# moduloComunicacao3.net
KiCad netlist of a schematic drawn in EAGLE
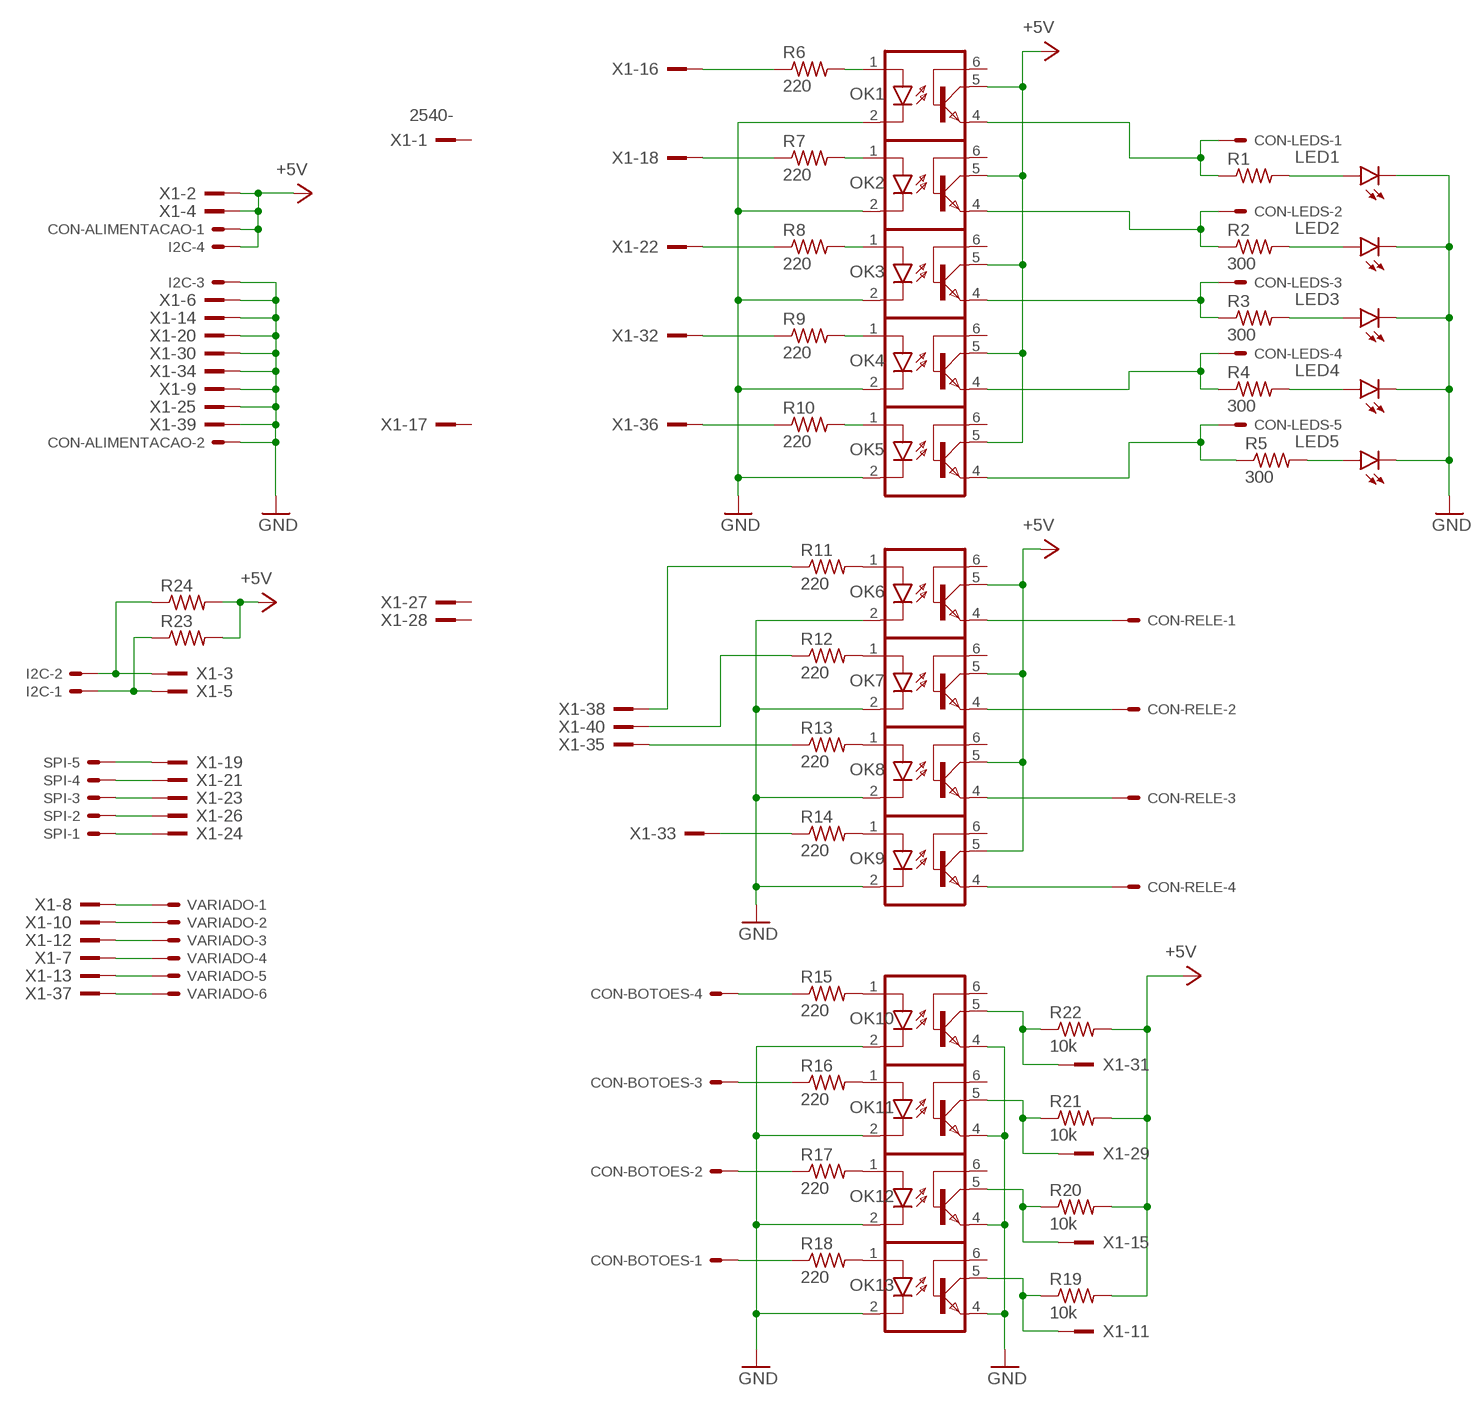
[diagram p0: schematic, sheet 1]

(export (version "E")
  (design (tool "Eeschema 10.0.6"))
  (components
    (comp (ref "CON-ALIMENTACAO")
      (value "22-23-2021")
      (footprint "eagle-import:22-23-2021")
      (fields (field (name "MF") "MOLEX"))
      (libsource (lib "eagle-import") (part "22-23-2021"))
    )
    (comp (ref "CON-BOTOES")
      (value "22-23-2041")
      (footprint "eagle-import:22-23-2041")
      (fields (field (name "MF") "MOLEX"))
      (libsource (lib "eagle-import") (part "22-23-2041"))
    )
    (comp (ref "CON-LEDS")
      (value "22-23-2051")
      (footprint "eagle-import:22-23-2051")
      (fields (field (name "MF") "MOLEX"))
      (libsource (lib "eagle-import") (part "22-23-2051"))
    )
    (comp (ref "CON-RELE")
      (value "22-23-2041")
      (footprint "eagle-import:22-23-2041")
      (fields (field (name "MF") "MOLEX"))
      (libsource (lib "eagle-import") (part "22-23-2041"))
    )
    (comp (ref "I2C")
      (value "22-23-2041")
      (footprint "eagle-import:22-23-2041")
      (fields (field (name "MF") "MOLEX"))
      (libsource (lib "eagle-import") (part "22-23-2041"))
    )
    (comp (ref "LED1")
      (value "LED5MM")
      (footprint "eagle-import:LED5MM")
      (libsource (lib "eagle-import") (part "LED5MM"))
    )
    (comp (ref "LED2")
      (value "LED5MM")
      (footprint "eagle-import:LED5MM")
      (libsource (lib "eagle-import") (part "LED5MM"))
    )
    (comp (ref "LED3")
      (value "LED5MM")
      (footprint "eagle-import:LED5MM")
      (libsource (lib "eagle-import") (part "LED5MM"))
    )
    (comp (ref "LED4")
      (value "LED5MM")
      (footprint "eagle-import:LED5MM")
      (libsource (lib "eagle-import") (part "LED5MM"))
    )
    (comp (ref "LED5")
      (value "LED5MM")
      (footprint "eagle-import:LED5MM")
      (libsource (lib "eagle-import") (part "LED5MM"))
    )
    (comp (ref "OK1")
      (value "4N25M")
      (footprint "eagle-import:DIL06")
      (fields (field (name "MPN") "4N25-M"))
      (libsource (lib "eagle-import") (part "4N?M25"))
    )
    (comp (ref "OK2")
      (value "4N25M")
      (footprint "eagle-import:DIL06")
      (fields (field (name "MPN") "4N25-M"))
      (libsource (lib "eagle-import") (part "4N?M25"))
    )
    (comp (ref "OK3")
      (value "4N25M")
      (footprint "eagle-import:DIL06")
      (fields (field (name "MPN") "4N25-M"))
      (libsource (lib "eagle-import") (part "4N?M25"))
    )
    (comp (ref "OK4")
      (value "4N25M")
      (footprint "eagle-import:DIL06")
      (fields (field (name "MPN") "4N25-M"))
      (libsource (lib "eagle-import") (part "4N?M25"))
    )
    (comp (ref "OK5")
      (value "4N25M")
      (footprint "eagle-import:DIL06")
      (fields (field (name "MPN") "4N25-M"))
      (libsource (lib "eagle-import") (part "4N?M25"))
    )
    (comp (ref "OK6")
      (value "4N25M")
      (footprint "eagle-import:DIL06")
      (fields (field (name "MPN") "4N25-M"))
      (libsource (lib "eagle-import") (part "4N?M25"))
    )
    (comp (ref "OK7")
      (value "4N25M")
      (footprint "eagle-import:DIL06")
      (fields (field (name "MPN") "4N25-M"))
      (libsource (lib "eagle-import") (part "4N?M25"))
    )
    (comp (ref "OK8")
      (value "4N25M")
      (footprint "eagle-import:DIL06")
      (fields (field (name "MPN") "4N25-M"))
      (libsource (lib "eagle-import") (part "4N?M25"))
    )
    (comp (ref "OK9")
      (value "4N25M")
      (footprint "eagle-import:DIL06")
      (fields (field (name "MPN") "4N25-M"))
      (libsource (lib "eagle-import") (part "4N?M25"))
    )
    (comp (ref "OK10")
      (value "4N25M")
      (footprint "eagle-import:DIL06")
      (fields (field (name "MPN") "4N25-M"))
      (libsource (lib "eagle-import") (part "4N?M25"))
    )
    (comp (ref "OK11")
      (value "4N25M")
      (footprint "eagle-import:DIL06")
      (fields (field (name "MPN") "4N25-M"))
      (libsource (lib "eagle-import") (part "4N?M25"))
    )
    (comp (ref "OK12")
      (value "4N25M")
      (footprint "eagle-import:DIL06")
      (fields (field (name "MPN") "4N25-M"))
      (libsource (lib "eagle-import") (part "4N?M25"))
    )
    (comp (ref "OK13")
      (value "4N25M")
      (footprint "eagle-import:DIL06")
      (fields (field (name "MPN") "4N25-M"))
      (libsource (lib "eagle-import") (part "4N?M25"))
    )
    (comp (ref "R1")
      (value "R-US_0207/12")
      (footprint "eagle-import:0207_12")
      (libsource (lib "eagle-import") (part "R-US_0207/12"))
    )
    (comp (ref "R2")
      (value "300")
      (footprint "eagle-import:0207_12")
      (libsource (lib "eagle-import") (part "R-US_0207/12"))
    )
    (comp (ref "R3")
      (value "300")
      (footprint "eagle-import:0207_12")
      (libsource (lib "eagle-import") (part "R-US_0207/12"))
    )
    (comp (ref "R4")
      (value "300")
      (footprint "eagle-import:0207_12")
      (libsource (lib "eagle-import") (part "R-US_0207/12"))
    )
    (comp (ref "R5")
      (value "300")
      (footprint "eagle-import:0207_12")
      (libsource (lib "eagle-import") (part "R-US_0207/12"))
    )
    (comp (ref "R6")
      (value "220")
      (footprint "eagle-import:0204_7")
      (libsource (lib "eagle-import") (part "R-US_0204/7"))
    )
    (comp (ref "R7")
      (value "220")
      (footprint "eagle-import:0204_7")
      (libsource (lib "eagle-import") (part "R-US_0204/7"))
    )
    (comp (ref "R8")
      (value "220")
      (footprint "eagle-import:0204_7")
      (libsource (lib "eagle-import") (part "R-US_0204/7"))
    )
    (comp (ref "R9")
      (value "220")
      (footprint "eagle-import:0204_7")
      (libsource (lib "eagle-import") (part "R-US_0204/7"))
    )
    (comp (ref "R10")
      (value "220")
      (footprint "eagle-import:0204_7")
      (libsource (lib "eagle-import") (part "R-US_0204/7"))
    )
    (comp (ref "R11")
      (value "220")
      (footprint "eagle-import:0204_7")
      (libsource (lib "eagle-import") (part "R-US_0204/7"))
    )
    (comp (ref "R12")
      (value "220")
      (footprint "eagle-import:0204_7")
      (libsource (lib "eagle-import") (part "R-US_0204/7"))
    )
    (comp (ref "R13")
      (value "220")
      (footprint "eagle-import:0204_7")
      (libsource (lib "eagle-import") (part "R-US_0204/7"))
    )
    (comp (ref "R14")
      (value "220")
      (footprint "eagle-import:0204_7")
      (libsource (lib "eagle-import") (part "R-US_0204/7"))
    )
    (comp (ref "R15")
      (value "220")
      (footprint "eagle-import:0207_10")
      (libsource (lib "eagle-import") (part "R-US_0207/10"))
    )
    (comp (ref "R16")
      (value "220")
      (footprint "eagle-import:0207_10")
      (libsource (lib "eagle-import") (part "R-US_0207/10"))
    )
    (comp (ref "R17")
      (value "220")
      (footprint "eagle-import:0207_10")
      (libsource (lib "eagle-import") (part "R-US_0207/10"))
    )
    (comp (ref "R18")
      (value "220")
      (footprint "eagle-import:0207_10")
      (libsource (lib "eagle-import") (part "R-US_0207/10"))
    )
    (comp (ref "R19")
      (value "10k")
      (footprint "eagle-import:0204_7")
      (libsource (lib "eagle-import") (part "R-US_0204/7"))
    )
    (comp (ref "R20")
      (value "10k")
      (footprint "eagle-import:0204_7")
      (libsource (lib "eagle-import") (part "R-US_0204/7"))
    )
    (comp (ref "R21")
      (value "10k")
      (footprint "eagle-import:0204_7")
      (libsource (lib "eagle-import") (part "R-US_0204/7"))
    )
    (comp (ref "R22")
      (value "10k")
      (footprint "eagle-import:0204_7")
      (libsource (lib "eagle-import") (part "R-US_0204/7"))
    )
    (comp (ref "R23")
      (value "R-US_0204/5")
      (footprint "eagle-import:0204_5")
      (libsource (lib "eagle-import") (part "R-US_0204/5"))
    )
    (comp (ref "R24")
      (value "R-US_0204/5")
      (footprint "eagle-import:0204_5")
      (libsource (lib "eagle-import") (part "R-US_0204/5"))
    )
    (comp (ref "SPI")
      (value "22-23-2051")
      (footprint "eagle-import:22-23-2051")
      (fields (field (name "MF") "MOLEX"))
      (libsource (lib "eagle-import") (part "22-23-2051"))
    )
    (comp (ref "VARIADO")
      (value "22-23-2061")
      (footprint "eagle-import:22-23-2061")
      (fields (field (name "MF") "MOLEX"))
      (libsource (lib "eagle-import") (part "22-23-2061"))
    )
    (comp (ref "X1")
      (value "2540-")
      (footprint "eagle-import:PAK100_2500-40")
      (libsource (lib "eagle-import") (part "2540-"))
    )
  )
  (nets
    (net (code "1") (name "+5V") (class "Default")
      (node (ref "CON-ALIMENTACAO") (pin "1") (pinfunction "S_1") (pintype "passive"))
      (node (ref "I2C") (pin "4") (pinfunction "S_4") (pintype "passive"))
      (node (ref "OK1") (pin "5") (pinfunction "COL_5") (pintype "passive"))
      (node (ref "OK2") (pin "5") (pinfunction "COL_5") (pintype "passive"))
      (node (ref "OK3") (pin "5") (pinfunction "COL_5") (pintype "passive"))
      (node (ref "OK4") (pin "5") (pinfunction "COL_5") (pintype "passive"))
      (node (ref "OK5") (pin "5") (pinfunction "COL_5") (pintype "passive"))
      (node (ref "OK6") (pin "5") (pinfunction "COL_5") (pintype "passive"))
      (node (ref "OK7") (pin "5") (pinfunction "COL_5") (pintype "passive"))
      (node (ref "OK8") (pin "5") (pinfunction "COL_5") (pintype "passive"))
      (node (ref "OK9") (pin "5") (pinfunction "COL_5") (pintype "passive"))
      (node (ref "R19") (pin "2") (pinfunction "2_2") (pintype "passive"))
      (node (ref "R20") (pin "2") (pinfunction "2_2") (pintype "passive"))
      (node (ref "R21") (pin "2") (pinfunction "2_2") (pintype "passive"))
      (node (ref "R22") (pin "2") (pinfunction "2_2") (pintype "passive"))
      (node (ref "R23") (pin "2") (pinfunction "2_2") (pintype "passive"))
      (node (ref "R24") (pin "2") (pinfunction "2_2") (pintype "passive"))
      (node (ref "X1") (pin "2") (pinfunction "KL_2") (pintype "passive"))
      (node (ref "X1") (pin "4") (pinfunction "KL_4") (pintype "passive"))
    )
    (net (code "2") (name "GND") (class "Default")
      (node (ref "CON-ALIMENTACAO") (pin "2") (pinfunction "S_2") (pintype "passive"))
      (node (ref "I2C") (pin "3") (pinfunction "S_3") (pintype "passive"))
      (node (ref "LED1") (pin "K") (pinfunction "C_K") (pintype "passive"))
      (node (ref "LED2") (pin "K") (pinfunction "C_K") (pintype "passive"))
      (node (ref "LED3") (pin "K") (pinfunction "C_K") (pintype "passive"))
      (node (ref "LED4") (pin "K") (pinfunction "C_K") (pintype "passive"))
      (node (ref "LED5") (pin "K") (pinfunction "C_K") (pintype "passive"))
      (node (ref "OK1") (pin "2") (pinfunction "C_2") (pintype "passive"))
      (node (ref "OK10") (pin "2") (pinfunction "C_2") (pintype "passive"))
      (node (ref "OK10") (pin "4") (pinfunction "EMI_4") (pintype "passive"))
      (node (ref "OK11") (pin "2") (pinfunction "C_2") (pintype "passive"))
      (node (ref "OK11") (pin "4") (pinfunction "EMI_4") (pintype "passive"))
      (node (ref "OK12") (pin "2") (pinfunction "C_2") (pintype "passive"))
      (node (ref "OK12") (pin "4") (pinfunction "EMI_4") (pintype "passive"))
      (node (ref "OK13") (pin "2") (pinfunction "C_2") (pintype "passive"))
      (node (ref "OK13") (pin "4") (pinfunction "EMI_4") (pintype "passive"))
      (node (ref "OK2") (pin "2") (pinfunction "C_2") (pintype "passive"))
      (node (ref "OK3") (pin "2") (pinfunction "C_2") (pintype "passive"))
      (node (ref "OK4") (pin "2") (pinfunction "C_2") (pintype "passive"))
      (node (ref "OK5") (pin "2") (pinfunction "C_2") (pintype "passive"))
      (node (ref "OK6") (pin "2") (pinfunction "C_2") (pintype "passive"))
      (node (ref "OK7") (pin "2") (pinfunction "C_2") (pintype "passive"))
      (node (ref "OK8") (pin "2") (pinfunction "C_2") (pintype "passive"))
      (node (ref "OK9") (pin "2") (pinfunction "C_2") (pintype "passive"))
      (node (ref "X1") (pin "14") (pinfunction "KL_14") (pintype "passive"))
      (node (ref "X1") (pin "20") (pinfunction "KL_20") (pintype "passive"))
      (node (ref "X1") (pin "25") (pinfunction "KL_25") (pintype "passive"))
      (node (ref "X1") (pin "30") (pinfunction "KL_30") (pintype "passive"))
      (node (ref "X1") (pin "34") (pinfunction "KL_34") (pintype "passive"))
      (node (ref "X1") (pin "39") (pinfunction "KL_39") (pintype "passive"))
      (node (ref "X1") (pin "6") (pinfunction "KL_6") (pintype "passive"))
      (node (ref "X1") (pin "9") (pinfunction "KL_9") (pintype "passive"))
    )
    (net (code "3") (name "Net-(CON-BOTOESA-S)") (class "Default")
      (node (ref "CON-BOTOES") (pin "1") (pinfunction "S_1") (pintype "passive"))
      (node (ref "R18") (pin "1") (pinfunction "1_1") (pintype "passive"))
    )
    (net (code "4") (name "Net-(CON-BOTOESB-S)") (class "Default")
      (node (ref "CON-BOTOES") (pin "2") (pinfunction "S_2") (pintype "passive"))
      (node (ref "R17") (pin "1") (pinfunction "1_1") (pintype "passive"))
    )
    (net (code "5") (name "Net-(CON-BOTOESC-S)") (class "Default")
      (node (ref "CON-BOTOES") (pin "3") (pinfunction "S_3") (pintype "passive"))
      (node (ref "R16") (pin "1") (pinfunction "1_1") (pintype "passive"))
    )
    (net (code "6") (name "Net-(CON-BOTOESD-S)") (class "Default")
      (node (ref "CON-BOTOES") (pin "4") (pinfunction "S_4") (pintype "passive"))
      (node (ref "R15") (pin "1") (pinfunction "1_1") (pintype "passive"))
    )
    (net (code "7") (name "Net-(CON-LEDSA-S)") (class "Default")
      (node (ref "CON-LEDS") (pin "1") (pinfunction "S_1") (pintype "passive"))
      (node (ref "OK1") (pin "4") (pinfunction "EMI_4") (pintype "passive"))
      (node (ref "R1") (pin "1") (pinfunction "1_1") (pintype "passive"))
    )
    (net (code "8") (name "Net-(CON-LEDSB-S)") (class "Default")
      (node (ref "CON-LEDS") (pin "2") (pinfunction "S_2") (pintype "passive"))
      (node (ref "OK2") (pin "4") (pinfunction "EMI_4") (pintype "passive"))
      (node (ref "R2") (pin "1") (pinfunction "1_1") (pintype "passive"))
    )
    (net (code "9") (name "Net-(CON-LEDSC-S)") (class "Default")
      (node (ref "CON-LEDS") (pin "3") (pinfunction "S_3") (pintype "passive"))
      (node (ref "OK3") (pin "4") (pinfunction "EMI_4") (pintype "passive"))
      (node (ref "R3") (pin "1") (pinfunction "1_1") (pintype "passive"))
    )
    (net (code "10") (name "Net-(CON-LEDSD-S)") (class "Default")
      (node (ref "CON-LEDS") (pin "4") (pinfunction "S_4") (pintype "passive"))
      (node (ref "OK4") (pin "4") (pinfunction "EMI_4") (pintype "passive"))
      (node (ref "R4") (pin "1") (pinfunction "1_1") (pintype "passive"))
    )
    (net (code "11") (name "Net-(CON-LEDSE-S)") (class "Default")
      (node (ref "CON-LEDS") (pin "5") (pinfunction "S_5") (pintype "passive"))
      (node (ref "OK5") (pin "4") (pinfunction "EMI_4") (pintype "passive"))
      (node (ref "R5") (pin "1") (pinfunction "1_1") (pintype "passive"))
    )
    (net (code "12") (name "Net-(CON-RELEA-S)") (class "Default")
      (node (ref "CON-RELE") (pin "1") (pinfunction "S_1") (pintype "passive"))
      (node (ref "OK6") (pin "4") (pinfunction "EMI_4") (pintype "passive"))
    )
    (net (code "13") (name "Net-(CON-RELEB-S)") (class "Default")
      (node (ref "CON-RELE") (pin "2") (pinfunction "S_2") (pintype "passive"))
      (node (ref "OK7") (pin "4") (pinfunction "EMI_4") (pintype "passive"))
    )
    (net (code "14") (name "Net-(CON-RELEC-S)") (class "Default")
      (node (ref "CON-RELE") (pin "3") (pinfunction "S_3") (pintype "passive"))
      (node (ref "OK8") (pin "4") (pinfunction "EMI_4") (pintype "passive"))
    )
    (net (code "15") (name "Net-(CON-RELED-S)") (class "Default")
      (node (ref "CON-RELE") (pin "4") (pinfunction "S_4") (pintype "passive"))
      (node (ref "OK9") (pin "4") (pinfunction "EMI_4") (pintype "passive"))
    )
    (net (code "16") (name "Net-(I2CA-S)") (class "Default")
      (node (ref "I2C") (pin "1") (pinfunction "S_1") (pintype "passive"))
      (node (ref "R23") (pin "1") (pinfunction "1_1") (pintype "passive"))
      (node (ref "X1") (pin "5") (pinfunction "KL_5") (pintype "passive"))
    )
    (net (code "17") (name "Net-(I2CB-S)") (class "Default")
      (node (ref "I2C") (pin "2") (pinfunction "S_2") (pintype "passive"))
      (node (ref "R24") (pin "1") (pinfunction "1_1") (pintype "passive"))
      (node (ref "X1") (pin "3") (pinfunction "KL_3") (pintype "passive"))
    )
    (net (code "18") (name "Net-(LED1-PadA)") (class "Default")
      (node (ref "LED1") (pin "A") (pinfunction "A_A") (pintype "passive"))
      (node (ref "R1") (pin "2") (pinfunction "2_2") (pintype "passive"))
    )
    (net (code "19") (name "Net-(LED2-PadA)") (class "Default")
      (node (ref "LED2") (pin "A") (pinfunction "A_A") (pintype "passive"))
      (node (ref "R2") (pin "2") (pinfunction "2_2") (pintype "passive"))
    )
    (net (code "20") (name "Net-(LED3-PadA)") (class "Default")
      (node (ref "LED3") (pin "A") (pinfunction "A_A") (pintype "passive"))
      (node (ref "R3") (pin "2") (pinfunction "2_2") (pintype "passive"))
    )
    (net (code "21") (name "Net-(LED4-PadA)") (class "Default")
      (node (ref "LED4") (pin "A") (pinfunction "A_A") (pintype "passive"))
      (node (ref "R4") (pin "2") (pinfunction "2_2") (pintype "passive"))
    )
    (net (code "22") (name "Net-(LED5-PadA)") (class "Default")
      (node (ref "LED5") (pin "A") (pinfunction "A_A") (pintype "passive"))
      (node (ref "R5") (pin "2") (pinfunction "2_2") (pintype "passive"))
    )
    (net (code "23") (name "Net-(OK1-A)") (class "Default")
      (node (ref "OK1") (pin "1") (pinfunction "A_1") (pintype "passive"))
      (node (ref "R6") (pin "2") (pinfunction "2_2") (pintype "passive"))
    )
    (net (code "24") (name "Net-(OK2-A)") (class "Default")
      (node (ref "OK2") (pin "1") (pinfunction "A_1") (pintype "passive"))
      (node (ref "R7") (pin "2") (pinfunction "2_2") (pintype "passive"))
    )
    (net (code "25") (name "Net-(OK3-A)") (class "Default")
      (node (ref "OK3") (pin "1") (pinfunction "A_1") (pintype "passive"))
      (node (ref "R8") (pin "2") (pinfunction "2_2") (pintype "passive"))
    )
    (net (code "26") (name "Net-(OK4-A)") (class "Default")
      (node (ref "OK4") (pin "1") (pinfunction "A_1") (pintype "passive"))
      (node (ref "R9") (pin "2") (pinfunction "2_2") (pintype "passive"))
    )
    (net (code "27") (name "Net-(OK5-A)") (class "Default")
      (node (ref "OK5") (pin "1") (pinfunction "A_1") (pintype "passive"))
      (node (ref "R10") (pin "2") (pinfunction "2_2") (pintype "passive"))
    )
    (net (code "28") (name "Net-(OK6-A)") (class "Default")
      (node (ref "OK6") (pin "1") (pinfunction "A_1") (pintype "passive"))
      (node (ref "R11") (pin "2") (pinfunction "2_2") (pintype "passive"))
    )
    (net (code "29") (name "Net-(OK7-A)") (class "Default")
      (node (ref "OK7") (pin "1") (pinfunction "A_1") (pintype "passive"))
      (node (ref "R12") (pin "2") (pinfunction "2_2") (pintype "passive"))
    )
    (net (code "30") (name "Net-(OK8-A)") (class "Default")
      (node (ref "OK8") (pin "1") (pinfunction "A_1") (pintype "passive"))
      (node (ref "R13") (pin "2") (pinfunction "2_2") (pintype "passive"))
    )
    (net (code "31") (name "Net-(OK9-A)") (class "Default")
      (node (ref "OK9") (pin "1") (pinfunction "A_1") (pintype "passive"))
      (node (ref "R14") (pin "2") (pinfunction "2_2") (pintype "passive"))
    )
    (net (code "32") (name "Net-(OK10-A)") (class "Default")
      (node (ref "OK10") (pin "1") (pinfunction "A_1") (pintype "passive"))
      (node (ref "R15") (pin "2") (pinfunction "2_2") (pintype "passive"))
    )
    (net (code "33") (name "Net-(OK10-COL)") (class "Default")
      (node (ref "OK10") (pin "5") (pinfunction "COL_5") (pintype "passive"))
      (node (ref "R22") (pin "1") (pinfunction "1_1") (pintype "passive"))
      (node (ref "X1") (pin "31") (pinfunction "KL_31") (pintype "passive"))
    )
    (net (code "34") (name "Net-(OK11-A)") (class "Default")
      (node (ref "OK11") (pin "1") (pinfunction "A_1") (pintype "passive"))
      (node (ref "R16") (pin "2") (pinfunction "2_2") (pintype "passive"))
    )
    (net (code "35") (name "Net-(OK11-COL)") (class "Default")
      (node (ref "OK11") (pin "5") (pinfunction "COL_5") (pintype "passive"))
      (node (ref "R21") (pin "1") (pinfunction "1_1") (pintype "passive"))
      (node (ref "X1") (pin "29") (pinfunction "KL_29") (pintype "passive"))
    )
    (net (code "36") (name "Net-(OK12-A)") (class "Default")
      (node (ref "OK12") (pin "1") (pinfunction "A_1") (pintype "passive"))
      (node (ref "R17") (pin "2") (pinfunction "2_2") (pintype "passive"))
    )
    (net (code "37") (name "Net-(OK12-COL)") (class "Default")
      (node (ref "OK12") (pin "5") (pinfunction "COL_5") (pintype "passive"))
      (node (ref "R20") (pin "1") (pinfunction "1_1") (pintype "passive"))
      (node (ref "X1") (pin "15") (pinfunction "KL_15") (pintype "passive"))
    )
    (net (code "38") (name "Net-(OK13-A)") (class "Default")
      (node (ref "OK13") (pin "1") (pinfunction "A_1") (pintype "passive"))
      (node (ref "R18") (pin "2") (pinfunction "2_2") (pintype "passive"))
    )
    (net (code "39") (name "Net-(OK13-COL)") (class "Default")
      (node (ref "OK13") (pin "5") (pinfunction "COL_5") (pintype "passive"))
      (node (ref "R19") (pin "1") (pinfunction "1_1") (pintype "passive"))
      (node (ref "X1") (pin "11") (pinfunction "KL_11") (pintype "passive"))
    )
    (net (code "40") (name "Net-(SPIA-S)") (class "Default")
      (node (ref "SPI") (pin "1") (pinfunction "S_1") (pintype "passive"))
      (node (ref "X1") (pin "24") (pinfunction "KL_24") (pintype "passive"))
    )
    (net (code "41") (name "Net-(SPIB-S)") (class "Default")
      (node (ref "SPI") (pin "2") (pinfunction "S_2") (pintype "passive"))
      (node (ref "X1") (pin "26") (pinfunction "KL_26") (pintype "passive"))
    )
    (net (code "42") (name "Net-(SPIC-S)") (class "Default")
      (node (ref "SPI") (pin "3") (pinfunction "S_3") (pintype "passive"))
      (node (ref "X1") (pin "23") (pinfunction "KL_23") (pintype "passive"))
    )
    (net (code "43") (name "Net-(SPID-S)") (class "Default")
      (node (ref "SPI") (pin "4") (pinfunction "S_4") (pintype "passive"))
      (node (ref "X1") (pin "21") (pinfunction "KL_21") (pintype "passive"))
    )
    (net (code "44") (name "Net-(SPIE-S)") (class "Default")
      (node (ref "SPI") (pin "5") (pinfunction "S_5") (pintype "passive"))
      (node (ref "X1") (pin "19") (pinfunction "KL_19") (pintype "passive"))
    )
    (net (code "45") (name "Net-(VARIADOA-S)") (class "Default")
      (node (ref "VARIADO") (pin "1") (pinfunction "S_1") (pintype "passive"))
      (node (ref "X1") (pin "8") (pinfunction "KL_8") (pintype "passive"))
    )
    (net (code "46") (name "Net-(VARIADOB-S)") (class "Default")
      (node (ref "VARIADO") (pin "2") (pinfunction "S_2") (pintype "passive"))
      (node (ref "X1") (pin "10") (pinfunction "KL_10") (pintype "passive"))
    )
    (net (code "47") (name "Net-(VARIADOC-S)") (class "Default")
      (node (ref "VARIADO") (pin "3") (pinfunction "S_3") (pintype "passive"))
      (node (ref "X1") (pin "12") (pinfunction "KL_12") (pintype "passive"))
    )
    (net (code "48") (name "Net-(VARIADOD-S)") (class "Default")
      (node (ref "VARIADO") (pin "4") (pinfunction "S_4") (pintype "passive"))
      (node (ref "X1") (pin "7") (pinfunction "KL_7") (pintype "passive"))
    )
    (net (code "49") (name "Net-(VARIADOE-S)") (class "Default")
      (node (ref "VARIADO") (pin "5") (pinfunction "S_5") (pintype "passive"))
      (node (ref "X1") (pin "13") (pinfunction "KL_13") (pintype "passive"))
    )
    (net (code "50") (name "Net-(VARIADOF-S)") (class "Default")
      (node (ref "VARIADO") (pin "6") (pinfunction "S_6") (pintype "passive"))
      (node (ref "X1") (pin "37") (pinfunction "KL_37") (pintype "passive"))
    )
    (net (code "51") (name "Net-(X1AA-KL)") (class "Default")
      (node (ref "R14") (pin "1") (pinfunction "1_1") (pintype "passive"))
      (node (ref "X1") (pin "33") (pinfunction "KL_33") (pintype "passive"))
    )
    (net (code "52") (name "Net-(X1AC-KL)") (class "Default")
      (node (ref "R13") (pin "1") (pinfunction "1_1") (pintype "passive"))
      (node (ref "X1") (pin "35") (pinfunction "KL_35") (pintype "passive"))
    )
    (net (code "53") (name "Net-(X1AD-KL)") (class "Default")
      (node (ref "R10") (pin "1") (pinfunction "1_1") (pintype "passive"))
      (node (ref "X1") (pin "36") (pinfunction "KL_36") (pintype "passive"))
    )
    (net (code "54") (name "Net-(X1AF-KL)") (class "Default")
      (node (ref "R11") (pin "1") (pinfunction "1_1") (pintype "passive"))
      (node (ref "X1") (pin "38") (pinfunction "KL_38") (pintype "passive"))
    )
    (net (code "55") (name "Net-(X1AI-KL)") (class "Default")
      (node (ref "R12") (pin "1") (pinfunction "1_1") (pintype "passive"))
      (node (ref "X1") (pin "40") (pinfunction "KL_40") (pintype "passive"))
    )
    (net (code "56") (name "Net-(X1H-KL)") (class "Default")
      (node (ref "R6") (pin "1") (pinfunction "1_1") (pintype "passive"))
      (node (ref "X1") (pin "16") (pinfunction "KL_16") (pintype "passive"))
    )
    (net (code "57") (name "Net-(X1J-KL)") (class "Default")
      (node (ref "R7") (pin "1") (pinfunction "1_1") (pintype "passive"))
      (node (ref "X1") (pin "18") (pinfunction "KL_18") (pintype "passive"))
    )
    (net (code "58") (name "Net-(X1O-KL)") (class "Default")
      (node (ref "R8") (pin "1") (pinfunction "1_1") (pintype "passive"))
      (node (ref "X1") (pin "22") (pinfunction "KL_22") (pintype "passive"))
    )
    (net (code "59") (name "Net-(X1Z-KL)") (class "Default")
      (node (ref "R9") (pin "1") (pinfunction "1_1") (pintype "passive"))
      (node (ref "X1") (pin "32") (pinfunction "KL_32") (pintype "passive"))
    )
    (net (code "60") (name "unconnected-(OK1-BAS-Pad6)") (class "Default")
      (node (ref "OK1") (pin "6") (pinfunction "BAS_6") (pintype "passive"))
    )
    (net (code "61") (name "unconnected-(OK2-BAS-Pad6)") (class "Default")
      (node (ref "OK2") (pin "6") (pinfunction "BAS_6") (pintype "passive"))
    )
    (net (code "62") (name "unconnected-(OK3-BAS-Pad6)") (class "Default")
      (node (ref "OK3") (pin "6") (pinfunction "BAS_6") (pintype "passive"))
    )
    (net (code "63") (name "unconnected-(OK4-BAS-Pad6)") (class "Default")
      (node (ref "OK4") (pin "6") (pinfunction "BAS_6") (pintype "passive"))
    )
    (net (code "64") (name "unconnected-(OK5-BAS-Pad6)") (class "Default")
      (node (ref "OK5") (pin "6") (pinfunction "BAS_6") (pintype "passive"))
    )
    (net (code "65") (name "unconnected-(OK6-BAS-Pad6)") (class "Default")
      (node (ref "OK6") (pin "6") (pinfunction "BAS_6") (pintype "passive"))
    )
    (net (code "66") (name "unconnected-(OK7-BAS-Pad6)") (class "Default")
      (node (ref "OK7") (pin "6") (pinfunction "BAS_6") (pintype "passive"))
    )
    (net (code "67") (name "unconnected-(OK8-BAS-Pad6)") (class "Default")
      (node (ref "OK8") (pin "6") (pinfunction "BAS_6") (pintype "passive"))
    )
    (net (code "68") (name "unconnected-(OK9-BAS-Pad6)") (class "Default")
      (node (ref "OK9") (pin "6") (pinfunction "BAS_6") (pintype "passive"))
    )
    (net (code "69") (name "unconnected-(OK10-BAS-Pad6)") (class "Default")
      (node (ref "OK10") (pin "6") (pinfunction "BAS_6") (pintype "passive"))
    )
    (net (code "70") (name "unconnected-(OK11-BAS-Pad6)") (class "Default")
      (node (ref "OK11") (pin "6") (pinfunction "BAS_6") (pintype "passive"))
    )
    (net (code "71") (name "unconnected-(OK12-BAS-Pad6)") (class "Default")
      (node (ref "OK12") (pin "6") (pinfunction "BAS_6") (pintype "passive"))
    )
    (net (code "72") (name "unconnected-(OK13-BAS-Pad6)") (class "Default")
      (node (ref "OK13") (pin "6") (pinfunction "BAS_6") (pintype "passive"))
    )
    (net (code "73") (name "unconnected-(X1A-KL-Pad1)") (class "Default")
      (node (ref "X1") (pin "1") (pinfunction "KL_1") (pintype "passive"))
    )
    (net (code "74") (name "unconnected-(X1I-KL-Pad17)") (class "Default")
      (node (ref "X1") (pin "17") (pinfunction "KL_17") (pintype "passive"))
    )
    (net (code "75") (name "unconnected-(X1T-KL-Pad27)") (class "Default")
      (node (ref "X1") (pin "27") (pinfunction "KL_27") (pintype "passive"))
    )
    (net (code "76") (name "unconnected-(X1U-KL-Pad28)") (class "Default")
      (node (ref "X1") (pin "28") (pinfunction "KL_28") (pintype "passive"))
    )
  )
)
